# BehaviorShield.net
KiCad netlist of a schematic drawn in EAGLE
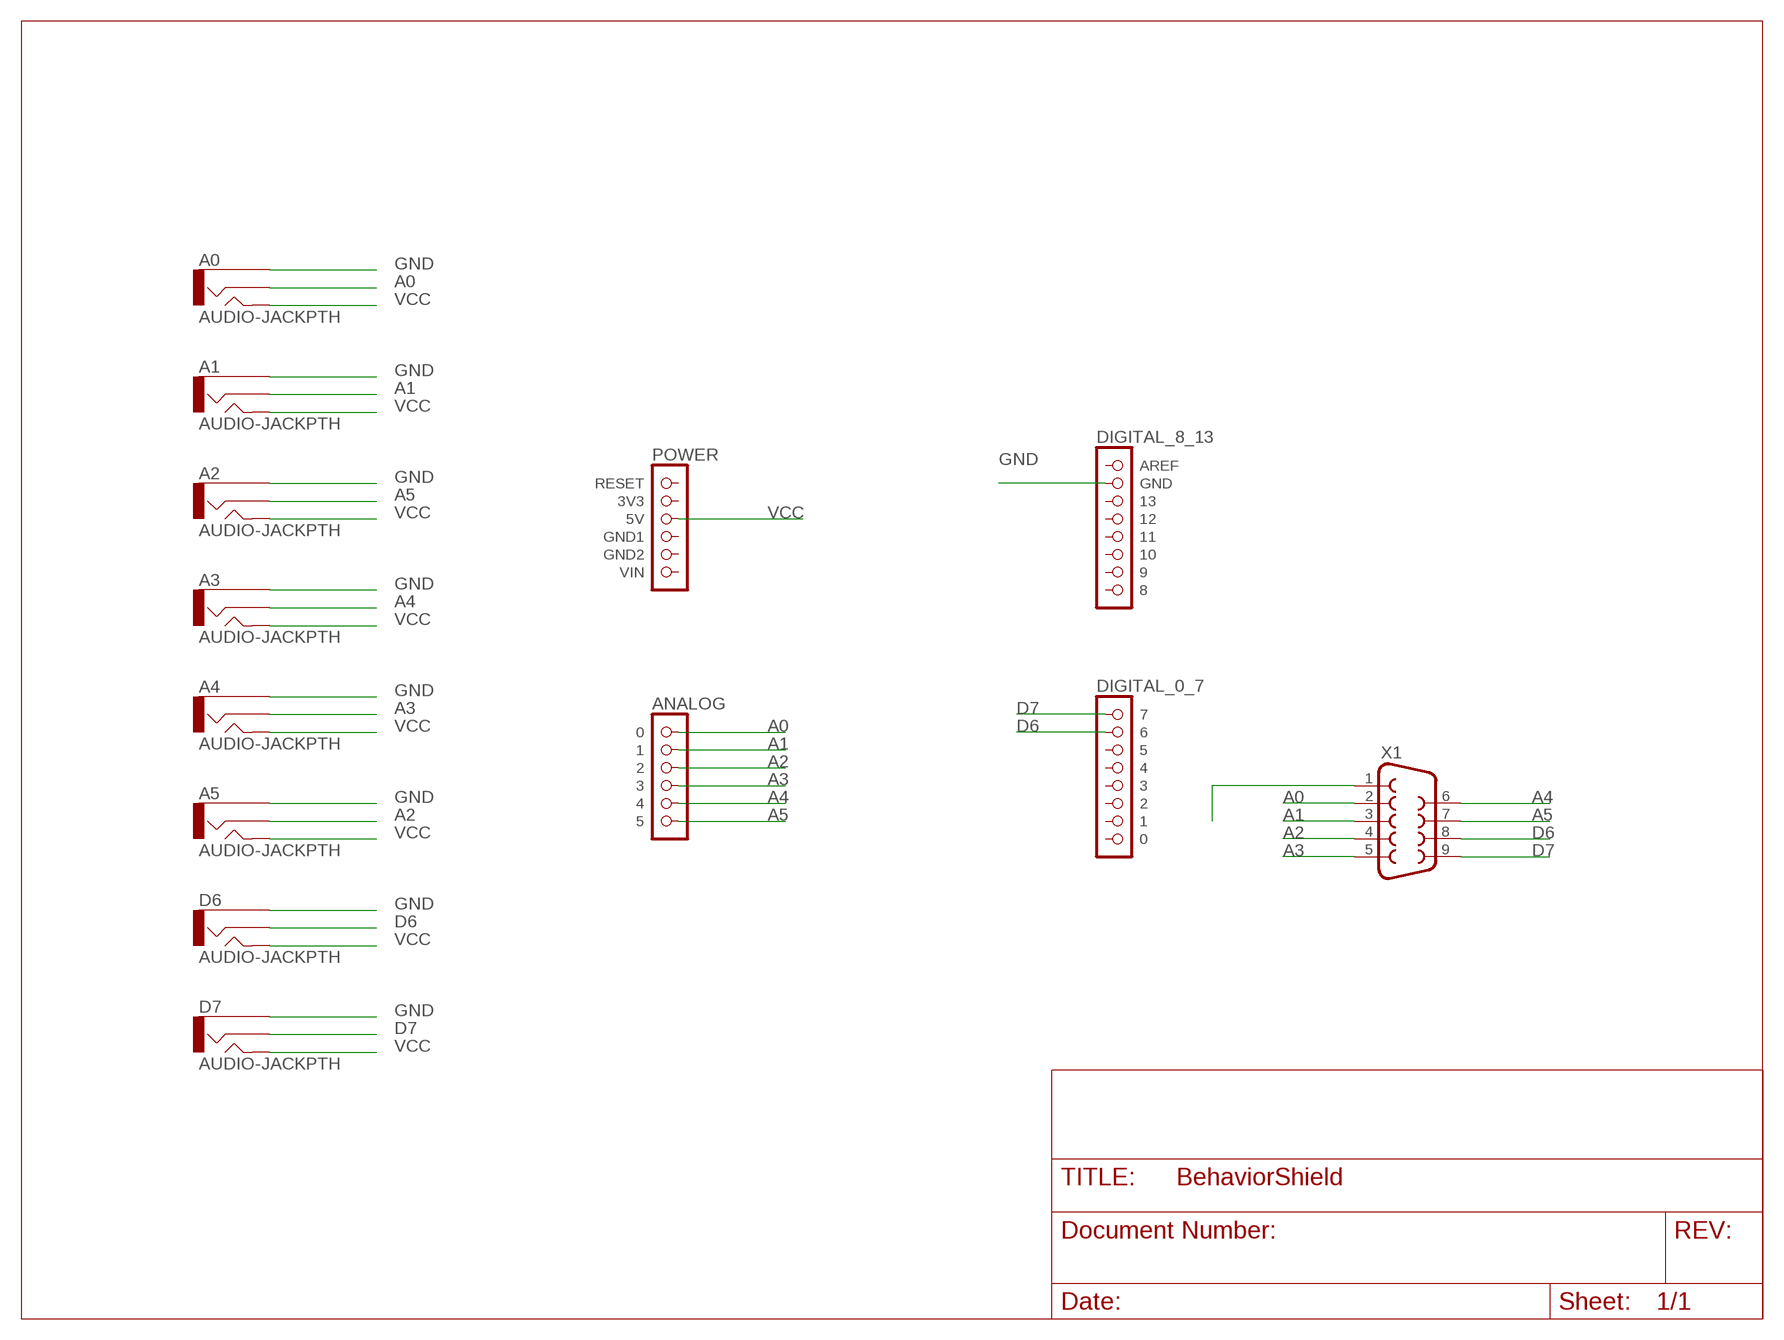
[diagram p0: schematic, sheet 1]

(export (version "E")
  (design (tool "Eeschema 10.0.6"))
  (components
    (comp (ref "A0")
      (value "AUDIO-JACKPTH")
      (footprint "eagle-import:AUDIO-JACK")
      (libsource (lib "eagle-import") (part "AUDIO-JACKPTH"))
    )
    (comp (ref "A1")
      (value "AUDIO-JACKPTH")
      (footprint "eagle-import:AUDIO-JACK")
      (libsource (lib "eagle-import") (part "AUDIO-JACKPTH"))
    )
    (comp (ref "A2")
      (value "AUDIO-JACKPTH")
      (footprint "eagle-import:AUDIO-JACK")
      (libsource (lib "eagle-import") (part "AUDIO-JACKPTH"))
    )
    (comp (ref "A3")
      (value "AUDIO-JACKPTH")
      (footprint "eagle-import:AUDIO-JACK")
      (libsource (lib "eagle-import") (part "AUDIO-JACKPTH"))
    )
    (comp (ref "A4")
      (value "AUDIO-JACKPTH")
      (footprint "eagle-import:AUDIO-JACK")
      (libsource (lib "eagle-import") (part "AUDIO-JACKPTH"))
    )
    (comp (ref "A5")
      (value "AUDIO-JACKPTH")
      (footprint "eagle-import:AUDIO-JACK")
      (libsource (lib "eagle-import") (part "AUDIO-JACKPTH"))
    )
    (comp (ref "D6")
      (value "AUDIO-JACKPTH")
      (footprint "eagle-import:AUDIO-JACK")
      (libsource (lib "eagle-import") (part "AUDIO-JACKPTH"))
    )
    (comp (ref "D7")
      (value "AUDIO-JACKPTH")
      (footprint "eagle-import:AUDIO-JACK")
      (libsource (lib "eagle-import") (part "AUDIO-JACKPTH"))
    )
    (comp (ref "U$1")
      (value "POWER")
      (footprint "eagle-import:1X06")
      (libsource (lib "eagle-import") (part "POWER"))
    )
    (comp (ref "U$2")
      (value "ANALOG")
      (footprint "eagle-import:1X06")
      (libsource (lib "eagle-import") (part "ANALOG"))
    )
    (comp (ref "U$3")
      (value "DIGITAL_0_7")
      (footprint "eagle-import:1X08")
      (libsource (lib "eagle-import") (part "DIGITAL_0_7"))
    )
    (comp (ref "U$4")
      (value "DIGITAL_8_13")
      (footprint "eagle-import:1X08")
      (libsource (lib "eagle-import") (part "DIGITAL_8_13"))
    )
    (comp (ref "X1")
      (value "F09HP")
      (footprint "eagle-import:F09HP")
      (libsource (lib "eagle-import") (part "F09HP"))
    )
  )
  (nets
    (net (code "1") (name "/A0") (class "Default")
      (node (ref "A0") (pin "2") (pinfunction "2_2") (pintype "bidirectional"))
      (node (ref "U$2") (pin "1") (pinfunction "0_1") (pintype "passive"))
      (node (ref "X1") (pin "2") (pinfunction "2_2") (pintype "passive"))
    )
    (net (code "2") (name "/A1") (class "Default")
      (node (ref "A1") (pin "2") (pinfunction "2_2") (pintype "bidirectional"))
      (node (ref "U$2") (pin "2") (pinfunction "1_2") (pintype "passive"))
      (node (ref "X1") (pin "3") (pinfunction "3_3") (pintype "passive"))
    )
    (net (code "3") (name "/A2") (class "Default")
      (node (ref "A5") (pin "2") (pinfunction "2_2") (pintype "bidirectional"))
      (node (ref "U$2") (pin "3") (pinfunction "2_3") (pintype "passive"))
      (node (ref "X1") (pin "4") (pinfunction "4_4") (pintype "passive"))
    )
    (net (code "4") (name "/A3") (class "Default")
      (node (ref "A4") (pin "2") (pinfunction "2_2") (pintype "bidirectional"))
      (node (ref "U$2") (pin "4") (pinfunction "3_4") (pintype "passive"))
      (node (ref "X1") (pin "5") (pinfunction "5_5") (pintype "passive"))
    )
    (net (code "5") (name "/A4") (class "Default")
      (node (ref "A3") (pin "2") (pinfunction "2_2") (pintype "bidirectional"))
      (node (ref "U$2") (pin "5") (pinfunction "4_5") (pintype "passive"))
      (node (ref "X1") (pin "6") (pinfunction "6_6") (pintype "passive"))
    )
    (net (code "6") (name "/A5") (class "Default")
      (node (ref "A2") (pin "2") (pinfunction "2_2") (pintype "bidirectional"))
      (node (ref "U$2") (pin "6") (pinfunction "5_6") (pintype "passive"))
      (node (ref "X1") (pin "7") (pinfunction "7_7") (pintype "passive"))
    )
    (net (code "7") (name "/D6") (class "Default")
      (node (ref "D6") (pin "2") (pinfunction "2_2") (pintype "bidirectional"))
      (node (ref "U$3") (pin "2") (pinfunction "6_2") (pintype "passive"))
      (node (ref "X1") (pin "8") (pinfunction "8_8") (pintype "passive"))
    )
    (net (code "8") (name "/D7") (class "Default")
      (node (ref "D7") (pin "2") (pinfunction "2_2") (pintype "bidirectional"))
      (node (ref "U$3") (pin "1") (pinfunction "7_1") (pintype "passive"))
      (node (ref "X1") (pin "9") (pinfunction "9_9") (pintype "passive"))
    )
    (net (code "9") (name "/GND") (class "Default")
      (node (ref "A0") (pin "1") (pinfunction "1_1") (pintype "bidirectional"))
      (node (ref "A1") (pin "1") (pinfunction "1_1") (pintype "bidirectional"))
      (node (ref "A2") (pin "1") (pinfunction "1_1") (pintype "bidirectional"))
      (node (ref "A3") (pin "1") (pinfunction "1_1") (pintype "bidirectional"))
      (node (ref "A4") (pin "1") (pinfunction "1_1") (pintype "bidirectional"))
      (node (ref "A5") (pin "1") (pinfunction "1_1") (pintype "bidirectional"))
      (node (ref "D6") (pin "1") (pinfunction "1_1") (pintype "bidirectional"))
      (node (ref "D7") (pin "1") (pinfunction "1_1") (pintype "bidirectional"))
      (node (ref "U$4") (pin "2") (pinfunction "GND_2") (pintype "passive"))
      (node (ref "X1") (pin "1") (pinfunction "1_1") (pintype "passive"))
    )
    (net (code "10") (name "/VCC") (class "Default")
      (node (ref "A0") (pin "5") (pinfunction "5_5") (pintype "bidirectional"))
      (node (ref "A1") (pin "5") (pinfunction "5_5") (pintype "bidirectional"))
      (node (ref "A2") (pin "5") (pinfunction "5_5") (pintype "bidirectional"))
      (node (ref "A3") (pin "5") (pinfunction "5_5") (pintype "bidirectional"))
      (node (ref "A4") (pin "5") (pinfunction "5_5") (pintype "bidirectional"))
      (node (ref "A5") (pin "5") (pinfunction "5_5") (pintype "bidirectional"))
      (node (ref "D6") (pin "5") (pinfunction "5_5") (pintype "bidirectional"))
      (node (ref "D7") (pin "5") (pinfunction "5_5") (pintype "bidirectional"))
      (node (ref "U$1") (pin "3") (pinfunction "5V_3") (pintype "passive"))
    )
    (net (code "11") (name "unconnected-(U$1-3V3-Pad2)") (class "Default")
      (node (ref "U$1") (pin "2") (pinfunction "3V3_2") (pintype "passive"))
    )
    (net (code "12") (name "unconnected-(U$1-GND1-Pad4)") (class "Default")
      (node (ref "U$1") (pin "4") (pinfunction "GND1_4") (pintype "passive"))
    )
    (net (code "13") (name "unconnected-(U$1-GND2-Pad5)") (class "Default")
      (node (ref "U$1") (pin "5") (pinfunction "GND2_5") (pintype "passive"))
    )
    (net (code "14") (name "unconnected-(U$1-RESET-Pad1)") (class "Default")
      (node (ref "U$1") (pin "1") (pinfunction "RESET_1") (pintype "passive"))
    )
    (net (code "15") (name "unconnected-(U$1-VIN-Pad6)") (class "Default")
      (node (ref "U$1") (pin "6") (pinfunction "VIN_6") (pintype "passive"))
    )
    (net (code "16") (name "unconnected-(U$3-0-Pad8)") (class "Default")
      (node (ref "U$3") (pin "8") (pinfunction "0_8") (pintype "passive"))
    )
    (net (code "17") (name "unconnected-(U$3-1-Pad7)") (class "Default")
      (node (ref "U$3") (pin "7") (pinfunction "1_7") (pintype "passive"))
    )
    (net (code "18") (name "unconnected-(U$3-2-Pad6)") (class "Default")
      (node (ref "U$3") (pin "6") (pinfunction "2_6") (pintype "passive"))
    )
    (net (code "19") (name "unconnected-(U$3-3-Pad5)") (class "Default")
      (node (ref "U$3") (pin "5") (pinfunction "3_5") (pintype "passive"))
    )
    (net (code "20") (name "unconnected-(U$3-5-Pad3)") (class "Default")
      (node (ref "U$3") (pin "3") (pinfunction "5_3") (pintype "passive"))
    )
    (net (code "21") (name "unconnected-(U$3-Pad4)") (class "Default")
      (node (ref "U$3") (pin "4") (pinfunction "4_4") (pintype "passive"))
    )
    (net (code "22") (name "unconnected-(U$4-9-Pad7)") (class "Default")
      (node (ref "U$4") (pin "7") (pinfunction "9_7") (pintype "passive"))
    )
    (net (code "23") (name "unconnected-(U$4-10-Pad6)") (class "Default")
      (node (ref "U$4") (pin "6") (pinfunction "10_6") (pintype "passive"))
    )
    (net (code "24") (name "unconnected-(U$4-11-Pad5)") (class "Default")
      (node (ref "U$4") (pin "5") (pinfunction "11_5") (pintype "passive"))
    )
    (net (code "25") (name "unconnected-(U$4-12-Pad4)") (class "Default")
      (node (ref "U$4") (pin "4") (pinfunction "12_4") (pintype "passive"))
    )
    (net (code "26") (name "unconnected-(U$4-13-Pad3)") (class "Default")
      (node (ref "U$4") (pin "3") (pinfunction "13_3") (pintype "passive"))
    )
    (net (code "27") (name "unconnected-(U$4-AREF-Pad1)") (class "Default")
      (node (ref "U$4") (pin "1") (pinfunction "AREF_1") (pintype "passive"))
    )
    (net (code "28") (name "unconnected-(U$4-Pad8)") (class "Default")
      (node (ref "U$4") (pin "8") (pinfunction "8_8") (pintype "passive"))
    )
  )
)
